# SCH_SlimeCircle_2024-09-21.net
KiCad netlist of a schematic drawn in EasyEDA
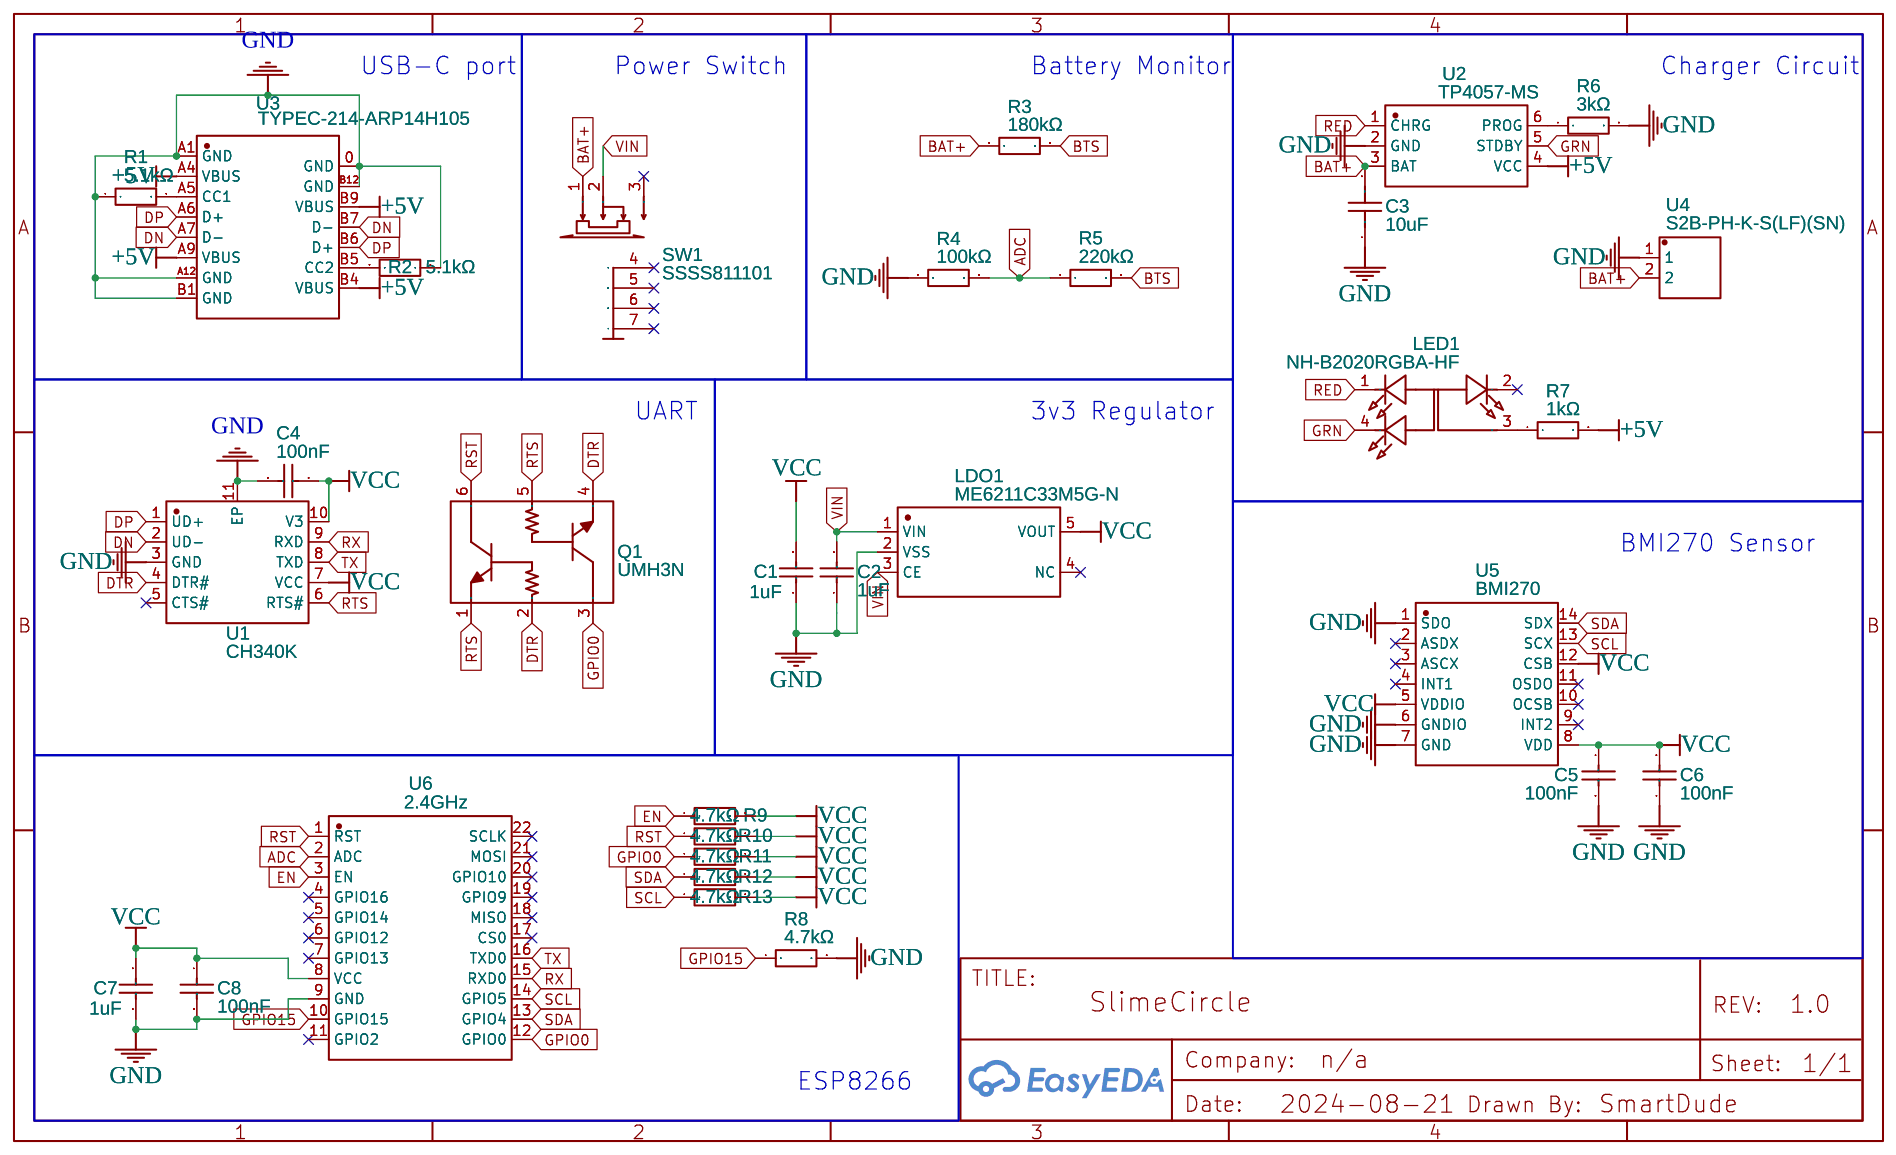
[diagram p0: schematic sheet]

(export (version "E")
  (design (tool "Eeschema 10.0.6"))
  (components
    (comp (ref "C1")
      (value "1uF")
      (fields
        (field (name "Manufacturer Part") "CL21B105KBFNNNE")
        (field (name "Manufacturer") "SAMSUNG(三星)")
      )
      (libsource (lib "") (part "CL21B105KBFNNNE"))
    )
    (comp (ref "C2")
      (value "1uF")
      (fields
        (field (name "Manufacturer Part") "CL21B105KBFNNNE")
        (field (name "Manufacturer") "SAMSUNG(三星)")
      )
      (libsource (lib "") (part "CL21B105KBFNNNE"))
    )
    (comp (ref "C3")
      (value "10uF")
      (fields
        (field (name "Manufacturer Part") "CL21A106KAYNNNE")
        (field (name "Manufacturer") "SAMSUNG(三星)")
      )
      (libsource (lib "") (part "CL21A106KAYNNNE"))
    )
    (comp (ref "C4")
      (value "100nF")
      (fields
        (field (name "Manufacturer Part") "CL21B104KCFNNNE")
        (field (name "Manufacturer") "SAMSUNG(三星)")
      )
      (libsource (lib "") (part "CL21B104KCFNNNE_2"))
    )
    (comp (ref "C5")
      (value "100nF")
      (fields
        (field (name "Manufacturer Part") "CL21B104KCFNNNE")
        (field (name "Manufacturer") "SAMSUNG(三星)")
      )
      (libsource (lib "") (part "CL21B104KCFNNNE_3"))
    )
    (comp (ref "C6")
      (value "100nF")
      (fields
        (field (name "Manufacturer Part") "CL21B104KCFNNNE")
        (field (name "Manufacturer") "SAMSUNG(三星)")
      )
      (libsource (lib "") (part "CL21B104KCFNNNE"))
    )
    (comp (ref "C7")
      (value "1uF")
      (fields
        (field (name "Manufacturer Part") "CL21B105KBFNNNE")
        (field (name "Manufacturer") "SAMSUNG(三星)")
      )
      (libsource (lib "") (part "CL21B105KBFNNNE"))
    )
    (comp (ref "C8")
      (value "100nF")
      (fields
        (field (name "Manufacturer Part") "CL21B104KCFNNNE")
        (field (name "Manufacturer") "SAMSUNG(三星)")
      )
      (libsource (lib "") (part "CL21B104KCFNNNE_1"))
    )
    (comp (ref "LDO1")
      (value "ME6211C33M5G-N")
      (fields (field (name "Manufacturer") "MICRONE(南京微盟)"))
      (libsource (lib "") (part "ME6211C33M5G-N"))
    )
    (comp (ref "LED1")
      (value "NH-B2020RGBA-HF")
      (fields (field (name "Manufacturer") "国星光电"))
      (libsource (lib "") (part "NH-B2020RGBA-HF"))
    )
    (comp (ref "Q1")
      (value "UMH3N")
      (fields (field (name "Manufacturer") "CJ(江苏长电/长晶)"))
      (libsource (lib "") (part "UMH3N"))
    )
    (comp (ref "R1")
      (value "5.1kΩ")
      (fields
        (field (name "Manufacturer Part") "0805W8F5101T5E")
        (field (name "Manufacturer") "UNI-ROYAL(厚声)")
      )
      (libsource (lib "") (part "0805W8F5101T5E"))
    )
    (comp (ref "R2")
      (value "5.1kΩ")
      (fields
        (field (name "Manufacturer Part") "0805W8F5101T5E")
        (field (name "Manufacturer") "UNI-ROYAL(厚声)")
      )
      (libsource (lib "") (part "0805W8F5101T5E_1"))
    )
    (comp (ref "R3")
      (value "180kΩ")
      (fields
        (field (name "Manufacturer Part") "0805W8F1803T5E")
        (field (name "Manufacturer") "UNI-ROYAL(厚声)")
      )
      (libsource (lib "") (part "0805W8F1803T5E"))
    )
    (comp (ref "R4")
      (value "100kΩ")
      (fields
        (field (name "Manufacturer Part") "0805W8F1003T5E")
        (field (name "Manufacturer") "UNI-ROYAL(厚声)")
      )
      (libsource (lib "") (part "0805W8F1003T5E_C149504"))
    )
    (comp (ref "R5")
      (value "220kΩ")
      (fields
        (field (name "Manufacturer Part") "0805W8F2203T5E")
        (field (name "Manufacturer") "UNI-ROYAL(厚声)")
      )
      (libsource (lib "") (part "0805W8F2203T5E"))
    )
    (comp (ref "R6")
      (value "3kΩ")
      (fields
        (field (name "Manufacturer Part") "0805W8F3001T5E")
        (field (name "Manufacturer") "UNI-ROYAL(厚声)")
      )
      (libsource (lib "") (part "0805W8F3001T5E"))
    )
    (comp (ref "R7")
      (value "1kΩ")
      (fields
        (field (name "Manufacturer Part") "0805W8F1001T5E")
        (field (name "Manufacturer") "UNI-ROYAL(厚声)")
      )
      (libsource (lib "") (part "0805W8F1001T5E"))
    )
    (comp (ref "R8")
      (value "4.7kΩ")
      (fields
        (field (name "Manufacturer Part") "0805W8F4701T5E")
        (field (name "Manufacturer") "UNI-ROYAL(厚声)")
      )
      (libsource (lib "") (part "0805W8F4701T5E"))
    )
    (comp (ref "R9")
      (value "4.7kΩ")
      (fields
        (field (name "Manufacturer Part") "0805W8F4701T5E")
        (field (name "Manufacturer") "UNI-ROYAL(厚声)")
      )
      (libsource (lib "") (part "0805W8F4701T5E"))
    )
    (comp (ref "R10")
      (value "4.7kΩ")
      (fields
        (field (name "Manufacturer Part") "0805W8F4701T5E")
        (field (name "Manufacturer") "UNI-ROYAL(厚声)")
      )
      (libsource (lib "") (part "0805W8F4701T5E"))
    )
    (comp (ref "R11")
      (value "4.7kΩ")
      (fields
        (field (name "Manufacturer Part") "0805W8F4701T5E")
        (field (name "Manufacturer") "UNI-ROYAL(厚声)")
      )
      (libsource (lib "") (part "0805W8F4701T5E"))
    )
    (comp (ref "R12")
      (value "4.7kΩ")
      (fields
        (field (name "Manufacturer Part") "0805W8F4701T5E")
        (field (name "Manufacturer") "UNI-ROYAL(厚声)")
      )
      (libsource (lib "") (part "0805W8F4701T5E"))
    )
    (comp (ref "R13")
      (value "4.7kΩ")
      (fields
        (field (name "Manufacturer Part") "0805W8F4701T5E")
        (field (name "Manufacturer") "UNI-ROYAL(厚声)")
      )
      (libsource (lib "") (part "0805W8F4701T5E"))
    )
    (comp (ref "SW1")
      (value "SSSS811101")
      (fields (field (name "Manufacturer") "ALPSALPINE(阿尔卑斯阿尔派)"))
      (libsource (lib "") (part "SSSS811101"))
    )
    (comp (ref "U1")
      (value "CH340K")
      (fields (field (name "Manufacturer") "WCH(南京沁恒)"))
      (libsource (lib "") (part "CH340K"))
    )
    (comp (ref "U2")
      (value "TP4057-MS")
      (fields (field (name "Manufacturer") "MSKSEMI(美森科)"))
      (libsource (lib "") (part "TP4057-MS"))
    )
    (comp (ref "U3")
      (value "TYPEC-214-ARP14H105")
      (fields (field (name "Manufacturer") "XUNPU(讯普)"))
      (libsource (lib "") (part "TYPEC-214-ARP14H105"))
    )
    (comp (ref "U4")
      (value "S2B-PH-K-S(LF)(SN)")
      (fields (field (name "Manufacturer") "JST"))
      (libsource (lib "") (part "S2B-PH-K-S(LF)(SN)"))
    )
    (comp (ref "U5")
      (value "BMI270")
      (fields (field (name "Manufacturer") "Bosch(博世)"))
      (libsource (lib "") (part "BMI270"))
    )
    (comp (ref "U6")
      (value "2.4GHz")
      (fields
        (field (name "Manufacturer Part") "ESP-12F(ESP8266MOD)")
        (field (name "Manufacturer") "Ai-Thinker(安信可)")
      )
      (libsource (lib "") (part "ESP-12F(ESP8266MOD)"))
    )
  )
  (nets
    (net (code "1") (name "+5V") (class "Default")
      (node (ref "R7") (pin "2") (pinfunction "2_2") (pintype "input"))
      (node (ref "U2") (pin "4") (pinfunction "VCC_4") (pintype "unspecified"))
      (node (ref "U3") (pin "A4") (pinfunction "VBUS_A4") (pintype "unspecified"))
      (node (ref "U3") (pin "A9") (pinfunction "VBUS_A9") (pintype "unspecified"))
      (node (ref "U3") (pin "B4") (pinfunction "VBUS_B4") (pintype "unspecified"))
      (node (ref "U3") (pin "B9") (pinfunction "VBUS_B9") (pintype "unspecified"))
    )
    (net (code "2") (name "ADC") (class "Default")
      (node (ref "R4") (pin "2") (pinfunction "2_2") (pintype "unspecified"))
      (node (ref "R5") (pin "1") (pinfunction "1_1") (pintype "input"))
      (node (ref "U6") (pin "2") (pinfunction "ADC_2") (pintype "unspecified"))
    )
    (net (code "3") (name "BAT+") (class "Default")
      (node (ref "C3") (pin "2") (pinfunction "2_2") (pintype "unspecified"))
      (node (ref "R3") (pin "1") (pinfunction "1_1") (pintype "input"))
      (node (ref "SW1") (pin "1") (pinfunction "1_1") (pintype "unspecified"))
      (node (ref "U2") (pin "3") (pinfunction "BAT_3") (pintype "unspecified"))
      (node (ref "U4") (pin "2") (pinfunction "2_2") (pintype "unspecified"))
    )
    (net (code "4") (name "BTS") (class "Default")
      (node (ref "R3") (pin "2") (pinfunction "2_2") (pintype "input"))
      (node (ref "R5") (pin "2") (pinfunction "2_2") (pintype "input"))
    )
    (net (code "5") (name "DN") (class "Default")
      (node (ref "U1") (pin "2") (pinfunction "UD-_2") (pintype "unspecified"))
      (node (ref "U3") (pin "A7") (pinfunction "D-_A7") (pintype "unspecified"))
      (node (ref "U3") (pin "B7") (pinfunction "D-_B7") (pintype "unspecified"))
    )
    (net (code "6") (name "DP") (class "Default")
      (node (ref "U1") (pin "1") (pinfunction "UD+_1") (pintype "unspecified"))
      (node (ref "U3") (pin "A6") (pinfunction "D+_A6") (pintype "unspecified"))
      (node (ref "U3") (pin "B6") (pinfunction "D+_B6") (pintype "unspecified"))
    )
    (net (code "7") (name "DTR") (class "Default")
      (node (ref "Q1") (pin "2") (pinfunction "B_2") (pintype "unspecified"))
      (node (ref "Q1") (pin "4") (pinfunction "E_4") (pintype "unspecified"))
      (node (ref "U1") (pin "4") (pinfunction "DTR#_4") (pintype "unspecified"))
    )
    (net (code "8") (name "EN") (class "Default")
      (node (ref "R9") (pin "1") (pinfunction "1_1") (pintype "input"))
      (node (ref "U6") (pin "3") (pinfunction "EN_3") (pintype "unspecified"))
    )
    (net (code "9") (name "GND") (class "Default")
      (node (ref "C1") (pin "1") (pinfunction "1_1") (pintype "input"))
      (node (ref "C2") (pin "1") (pinfunction "1_1") (pintype "input"))
      (node (ref "C3") (pin "1") (pinfunction "1_1") (pintype "unspecified"))
      (node (ref "C4") (pin "1") (pinfunction "1_1") (pintype "input"))
      (node (ref "C5") (pin "2") (pinfunction "2_2") (pintype "input"))
      (node (ref "C6") (pin "1") (pinfunction "1_1") (pintype "input"))
      (node (ref "C7") (pin "1") (pinfunction "1_1") (pintype "input"))
      (node (ref "C8") (pin "2") (pinfunction "2_2") (pintype "input"))
      (node (ref "LDO1") (pin "2") (pinfunction "VSS_2") (pintype "unspecified"))
      (node (ref "R1") (pin "1") (pinfunction "1_1") (pintype "input"))
      (node (ref "R2") (pin "1") (pinfunction "1_1") (pintype "input"))
      (node (ref "R4") (pin "1") (pinfunction "1_1") (pintype "unspecified"))
      (node (ref "R6") (pin "2") (pinfunction "2_2") (pintype "input"))
      (node (ref "R8") (pin "2") (pinfunction "2_2") (pintype "input"))
      (node (ref "U1") (pin "11") (pinfunction "EP_11") (pintype "unspecified"))
      (node (ref "U1") (pin "3") (pinfunction "GND_3") (pintype "unspecified"))
      (node (ref "U2") (pin "2") (pinfunction "GND_2") (pintype "unspecified"))
      (node (ref "U3") (pin "0") (pinfunction "GND_0") (pintype "unspecified"))
      (node (ref "U3") (pin "A1") (pinfunction "GND_A1") (pintype "unspecified"))
      (node (ref "U3") (pin "A12") (pinfunction "GND_A12") (pintype "unspecified"))
      (node (ref "U3") (pin "B1") (pinfunction "GND_B1") (pintype "unspecified"))
      (node (ref "U3") (pin "B12") (pinfunction "GND_B12") (pintype "unspecified"))
      (node (ref "U4") (pin "1") (pinfunction "1_1") (pintype "unspecified"))
      (node (ref "U5") (pin "1") (pinfunction "SDO_1") (pintype "unspecified"))
      (node (ref "U5") (pin "6") (pinfunction "GNDIO_6") (pintype "unspecified"))
      (node (ref "U5") (pin "7") (pinfunction "GND_7") (pintype "unspecified"))
      (node (ref "U6") (pin "9") (pinfunction "GND_9") (pintype "unspecified"))
    )
    (net (code "10") (name "GPIO0") (class "Default")
      (node (ref "Q1") (pin "3") (pinfunction "C_3") (pintype "unspecified"))
      (node (ref "R11") (pin "1") (pinfunction "1_1") (pintype "input"))
      (node (ref "U6") (pin "12") (pinfunction "GPIO0_12") (pintype "unspecified"))
    )
    (net (code "11") (name "GPIO15") (class "Default")
      (node (ref "R8") (pin "1") (pinfunction "1_1") (pintype "input"))
      (node (ref "U6") (pin "10") (pinfunction "GPIO15_10") (pintype "unspecified"))
    )
    (net (code "12") (name "GRN") (class "Default")
      (node (ref "LED1") (pin "4") (pinfunction "-_4") (pintype "unspecified"))
      (node (ref "U2") (pin "5") (pinfunction "STDBY_5") (pintype "unspecified"))
    )
    (net (code "13") (name "Net-(LED1-+)") (class "Default")
      (node (ref "LED1") (pin "3") (pinfunction "+_3") (pintype "unspecified"))
      (node (ref "R7") (pin "1") (pinfunction "1_1") (pintype "input"))
    )
    (net (code "14") (name "Net-(U2-PROG)") (class "Default")
      (node (ref "R6") (pin "1") (pinfunction "1_1") (pintype "input"))
      (node (ref "U2") (pin "6") (pinfunction "PROG_6") (pintype "unspecified"))
    )
    (net (code "15") (name "Net-(U3-CC1)") (class "Default")
      (node (ref "R1") (pin "2") (pinfunction "2_2") (pintype "input"))
      (node (ref "U3") (pin "A5") (pinfunction "CC1_A5") (pintype "unspecified"))
    )
    (net (code "16") (name "Net-(U3-CC2)") (class "Default")
      (node (ref "R2") (pin "2") (pinfunction "2_2") (pintype "input"))
      (node (ref "U3") (pin "B5") (pinfunction "CC2_B5") (pintype "unspecified"))
    )
    (net (code "17") (name "RED") (class "Default")
      (node (ref "LED1") (pin "1") (pinfunction "-_1") (pintype "unspecified"))
      (node (ref "U2") (pin "1") (pinfunction "CHRG_1") (pintype "unspecified"))
    )
    (net (code "18") (name "RST") (class "Default")
      (node (ref "Q1") (pin "6") (pinfunction "C_6") (pintype "unspecified"))
      (node (ref "R10") (pin "1") (pinfunction "1_1") (pintype "input"))
      (node (ref "U6") (pin "1") (pinfunction "RST_1") (pintype "unspecified"))
    )
    (net (code "19") (name "RTS") (class "Default")
      (node (ref "Q1") (pin "1") (pinfunction "E_1") (pintype "unspecified"))
      (node (ref "Q1") (pin "5") (pinfunction "B_5") (pintype "unspecified"))
      (node (ref "U1") (pin "6") (pinfunction "RTS#_6") (pintype "unspecified"))
    )
    (net (code "20") (name "RX") (class "Default")
      (node (ref "U1") (pin "9") (pinfunction "RXD_9") (pintype "unspecified"))
      (node (ref "U6") (pin "15") (pinfunction "RXD0_15") (pintype "unspecified"))
    )
    (net (code "21") (name "SCL") (class "Default")
      (node (ref "R13") (pin "1") (pinfunction "1_1") (pintype "input"))
      (node (ref "U5") (pin "13") (pinfunction "SCX_13") (pintype "unspecified"))
      (node (ref "U6") (pin "14") (pinfunction "GPIO5_14") (pintype "unspecified"))
    )
    (net (code "22") (name "SDA") (class "Default")
      (node (ref "R12") (pin "1") (pinfunction "1_1") (pintype "input"))
      (node (ref "U5") (pin "14") (pinfunction "SDX_14") (pintype "unspecified"))
      (node (ref "U6") (pin "13") (pinfunction "GPIO4_13") (pintype "unspecified"))
    )
    (net (code "23") (name "TX") (class "Default")
      (node (ref "U1") (pin "8") (pinfunction "TXD_8") (pintype "unspecified"))
      (node (ref "U6") (pin "16") (pinfunction "TXD0_16") (pintype "unspecified"))
    )
    (net (code "24") (name "VCC") (class "Default")
      (node (ref "C1") (pin "2") (pinfunction "2_2") (pintype "input"))
      (node (ref "C4") (pin "2") (pinfunction "2_2") (pintype "input"))
      (node (ref "C5") (pin "1") (pinfunction "1_1") (pintype "input"))
      (node (ref "C6") (pin "2") (pinfunction "2_2") (pintype "input"))
      (node (ref "C7") (pin "2") (pinfunction "2_2") (pintype "input"))
      (node (ref "C8") (pin "1") (pinfunction "1_1") (pintype "input"))
      (node (ref "LDO1") (pin "5") (pinfunction "VOUT_5") (pintype "unspecified"))
      (node (ref "R10") (pin "2") (pinfunction "2_2") (pintype "input"))
      (node (ref "R11") (pin "2") (pinfunction "2_2") (pintype "input"))
      (node (ref "R12") (pin "2") (pinfunction "2_2") (pintype "input"))
      (node (ref "R13") (pin "2") (pinfunction "2_2") (pintype "input"))
      (node (ref "R9") (pin "2") (pinfunction "2_2") (pintype "input"))
      (node (ref "U1") (pin "10") (pinfunction "V3_10") (pintype "unspecified"))
      (node (ref "U1") (pin "7") (pinfunction "VCC_7") (pintype "unspecified"))
      (node (ref "U5") (pin "12") (pinfunction "CSB_12") (pintype "unspecified"))
      (node (ref "U5") (pin "5") (pinfunction "VDDIO_5") (pintype "unspecified"))
      (node (ref "U5") (pin "8") (pinfunction "VDD_8") (pintype "unspecified"))
      (node (ref "U6") (pin "8") (pinfunction "VCC_8") (pintype "unspecified"))
    )
    (net (code "25") (name "VIN") (class "Default")
      (node (ref "C2") (pin "2") (pinfunction "2_2") (pintype "input"))
      (node (ref "LDO1") (pin "1") (pinfunction "VIN_1") (pintype "unspecified"))
      (node (ref "LDO1") (pin "3") (pinfunction "CE_3") (pintype "unspecified"))
      (node (ref "SW1") (pin "2") (pinfunction "2_2") (pintype "unspecified"))
    )
    (net (code "26") (name "unconnected-(LDO1-NC-Pad4)") (class "Default")
      (node (ref "LDO1") (pin "4") (pinfunction "NC_4") (pintype "unspecified+no_connect"))
    )
    (net (code "27") (name "unconnected-(LED1---Pad2)") (class "Default")
      (node (ref "LED1") (pin "2") (pinfunction "-_2") (pintype "unspecified+no_connect"))
    )
    (net (code "28") (name "unconnected-(SW1-Pad3)") (class "Default")
      (node (ref "SW1") (pin "3") (pinfunction "3_3") (pintype "unspecified+no_connect"))
    )
    (net (code "29") (name "unconnected-(SW1-Pad4)") (class "Default")
      (node (ref "SW1") (pin "4") (pinfunction "4_4") (pintype "unspecified+no_connect"))
    )
    (net (code "30") (name "unconnected-(SW1-Pad5)") (class "Default")
      (node (ref "SW1") (pin "5") (pinfunction "5_5") (pintype "unspecified+no_connect"))
    )
    (net (code "31") (name "unconnected-(SW1-Pad6)") (class "Default")
      (node (ref "SW1") (pin "6") (pinfunction "6_6") (pintype "unspecified+no_connect"))
    )
    (net (code "32") (name "unconnected-(SW1-Pad7)") (class "Default")
      (node (ref "SW1") (pin "7") (pinfunction "7_7") (pintype "unspecified+no_connect"))
    )
    (net (code "33") (name "unconnected-(U1-CTS#-Pad5)") (class "Default")
      (node (ref "U1") (pin "5") (pinfunction "CTS#_5") (pintype "unspecified+no_connect"))
    )
    (net (code "34") (name "unconnected-(U5-ASCX-Pad3)") (class "Default")
      (node (ref "U5") (pin "3") (pinfunction "ASCX_3") (pintype "unspecified+no_connect"))
    )
    (net (code "35") (name "unconnected-(U5-ASDX-Pad2)") (class "Default")
      (node (ref "U5") (pin "2") (pinfunction "ASDX_2") (pintype "unspecified+no_connect"))
    )
    (net (code "36") (name "unconnected-(U5-INT1-Pad4)") (class "Default")
      (node (ref "U5") (pin "4") (pinfunction "INT1_4") (pintype "unspecified+no_connect"))
    )
    (net (code "37") (name "unconnected-(U5-INT2-Pad9)") (class "Default")
      (node (ref "U5") (pin "9") (pinfunction "INT2_9") (pintype "unspecified+no_connect"))
    )
    (net (code "38") (name "unconnected-(U5-OCSB-Pad10)") (class "Default")
      (node (ref "U5") (pin "10") (pinfunction "OCSB_10") (pintype "unspecified+no_connect"))
    )
    (net (code "39") (name "unconnected-(U5-OSDO-Pad11)") (class "Default")
      (node (ref "U5") (pin "11") (pinfunction "OSDO_11") (pintype "unspecified+no_connect"))
    )
    (net (code "40") (name "unconnected-(U6-CS0-Pad17)") (class "Default")
      (node (ref "U6") (pin "17") (pinfunction "CS0_17") (pintype "unspecified+no_connect"))
    )
    (net (code "41") (name "unconnected-(U6-GPIO2-Pad11)") (class "Default")
      (node (ref "U6") (pin "11") (pinfunction "GPIO2_11") (pintype "unspecified+no_connect"))
    )
    (net (code "42") (name "unconnected-(U6-GPIO9-Pad19)") (class "Default")
      (node (ref "U6") (pin "19") (pinfunction "GPIO9_19") (pintype "unspecified+no_connect"))
    )
    (net (code "43") (name "unconnected-(U6-GPIO10-Pad20)") (class "Default")
      (node (ref "U6") (pin "20") (pinfunction "GPIO10_20") (pintype "unspecified+no_connect"))
    )
    (net (code "44") (name "unconnected-(U6-GPIO12-Pad6)") (class "Default")
      (node (ref "U6") (pin "6") (pinfunction "GPIO12_6") (pintype "unspecified+no_connect"))
    )
    (net (code "45") (name "unconnected-(U6-GPIO13-Pad7)") (class "Default")
      (node (ref "U6") (pin "7") (pinfunction "GPIO13_7") (pintype "unspecified+no_connect"))
    )
    (net (code "46") (name "unconnected-(U6-GPIO14-Pad5)") (class "Default")
      (node (ref "U6") (pin "5") (pinfunction "GPIO14_5") (pintype "unspecified+no_connect"))
    )
    (net (code "47") (name "unconnected-(U6-GPIO16-Pad4)") (class "Default")
      (node (ref "U6") (pin "4") (pinfunction "GPIO16_4") (pintype "unspecified+no_connect"))
    )
    (net (code "48") (name "unconnected-(U6-MISO-Pad18)") (class "Default")
      (node (ref "U6") (pin "18") (pinfunction "MISO_18") (pintype "unspecified+no_connect"))
    )
    (net (code "49") (name "unconnected-(U6-MOSI-Pad21)") (class "Default")
      (node (ref "U6") (pin "21") (pinfunction "MOSI_21") (pintype "unspecified+no_connect"))
    )
    (net (code "50") (name "unconnected-(U6-SCLK-Pad22)") (class "Default")
      (node (ref "U6") (pin "22") (pinfunction "SCLK_22") (pintype "unspecified+no_connect"))
    )
  )
)
